# Macropad.net
KiCad netlist of a schematic drawn in EAGLE
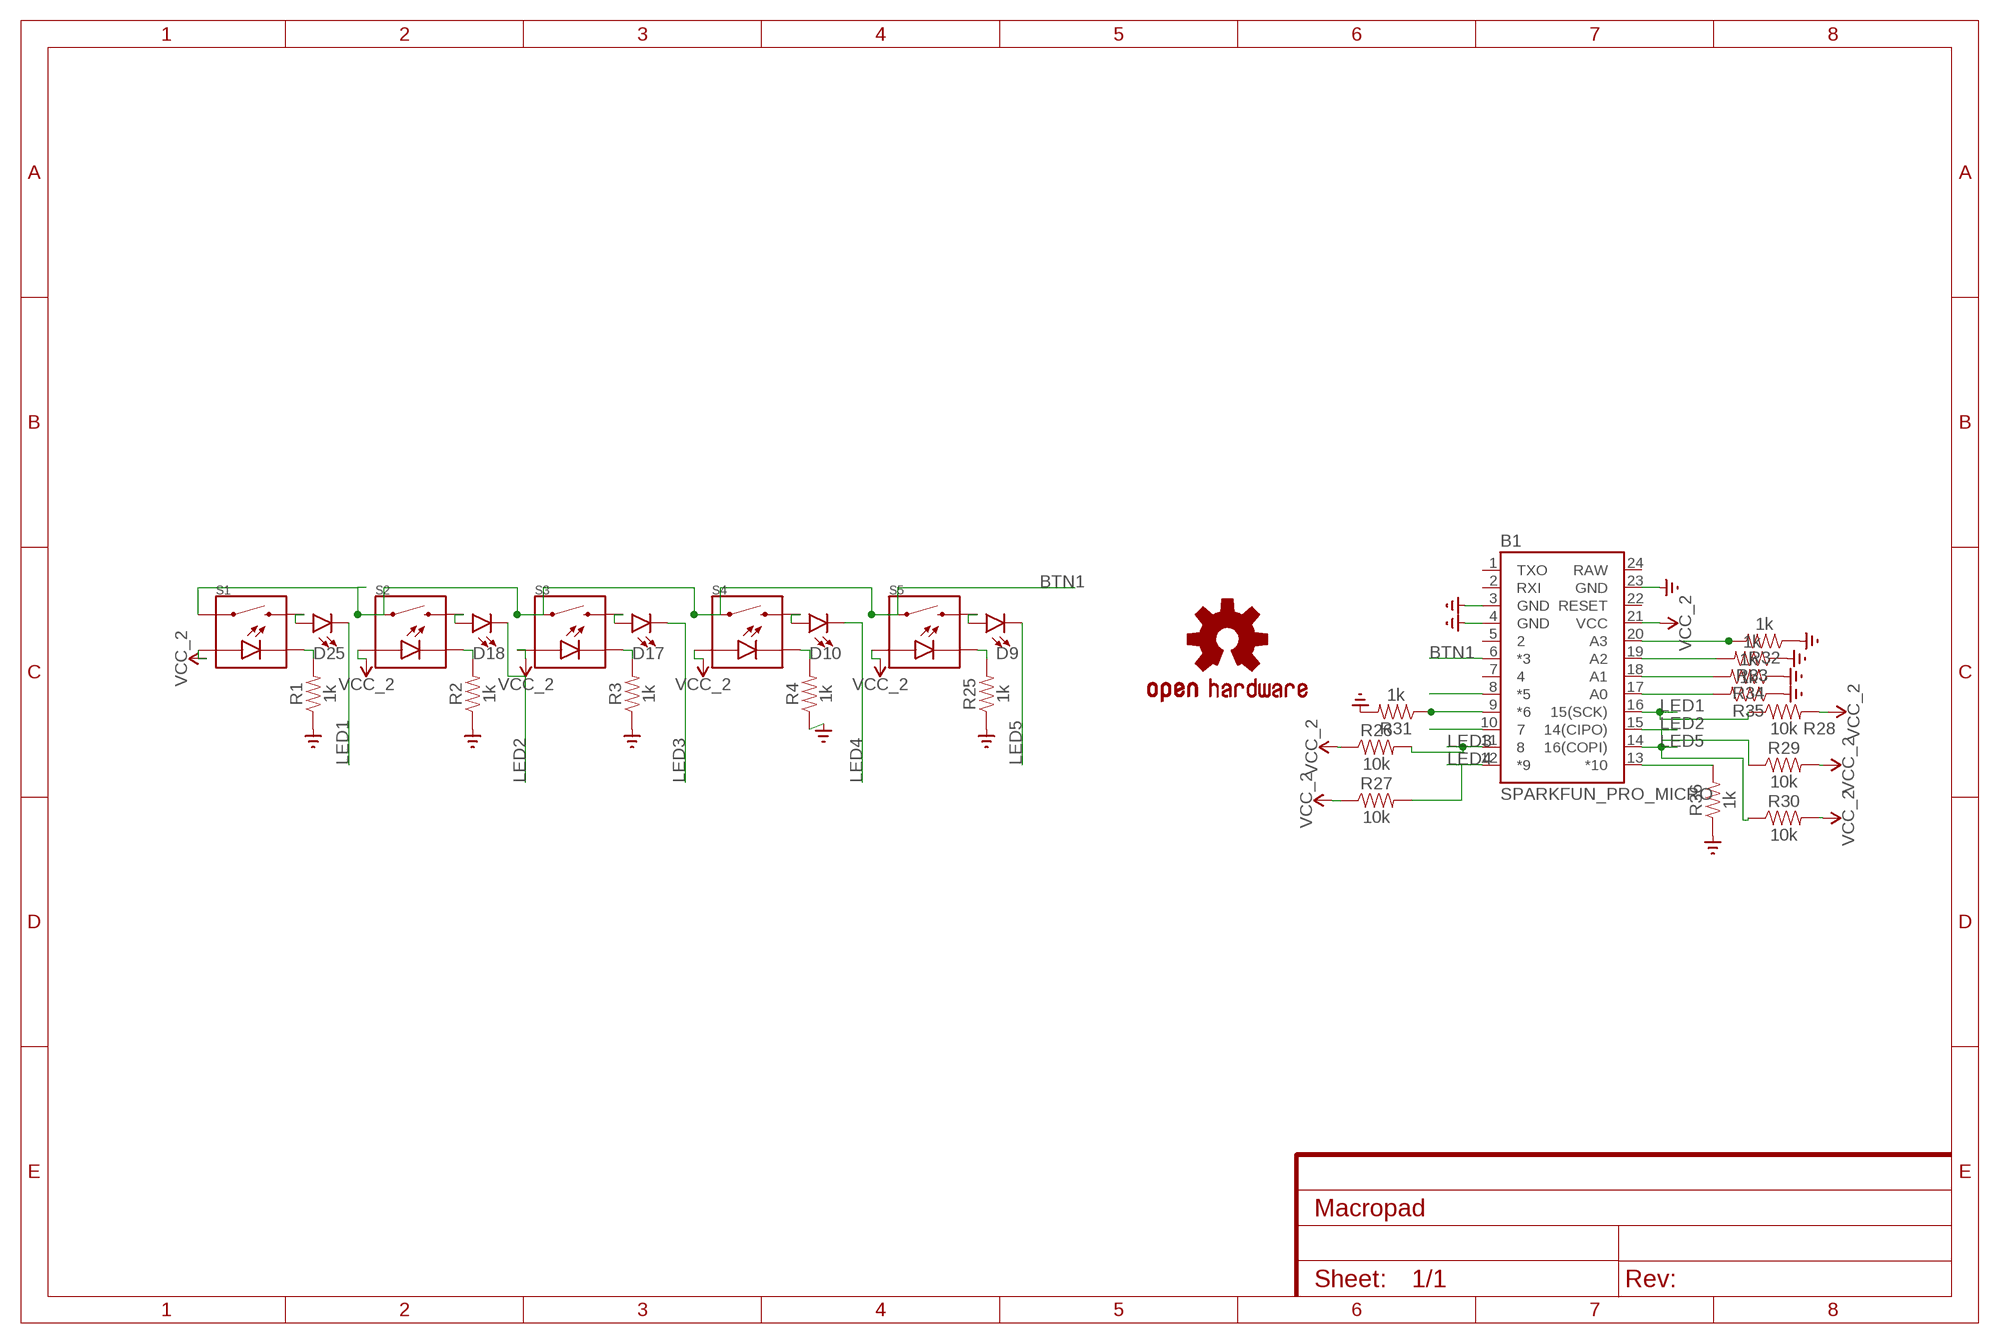
[diagram p0: schematic, sheet 1]

(export (version "E")
  (design (tool "Eeschema 10.0.6"))
  (components
    (comp (ref "B1")
      (value "SPARKFUN_PRO_MICRO")
      (footprint "eagle-import:SPARKFUN_PRO_MICRO")
      (libsource (lib "eagle-import") (part "SPARKFUN_PRO_MICRO"))
    )
    (comp (ref "D9")
      (value "LED3MM")
      (footprint "eagle-import:LED_3MM")
      (libsource (lib "eagle-import") (part "LED3MM"))
    )
    (comp (ref "D10")
      (value "LED3MM")
      (footprint "eagle-import:LED_3MM")
      (libsource (lib "eagle-import") (part "LED3MM"))
    )
    (comp (ref "D17")
      (value "LED3MM")
      (footprint "eagle-import:LED_3MM")
      (libsource (lib "eagle-import") (part "LED3MM"))
    )
    (comp (ref "D18")
      (value "LED3MM")
      (footprint "eagle-import:LED_3MM")
      (libsource (lib "eagle-import") (part "LED3MM"))
    )
    (comp (ref "D25")
      (value "LED3MM")
      (footprint "eagle-import:LED_3MM")
      (libsource (lib "eagle-import") (part "LED3MM"))
    )
    (comp (ref "LOGO1")
      (value "OSHW-LOGOM-COPPER")
      (footprint "eagle-import:OSHW-LOGO-M_COPPER")
      (libsource (lib "eagle-import") (part "OSHW-LOGOM-COPPER"))
    )
    (comp (ref "R1")
      (value "1k")
      (footprint "eagle-import:AXIAL-0.3")
      (libsource (lib "eagle-import") (part "1KOHM-HORIZ-1/4W-1%"))
    )
    (comp (ref "R2")
      (value "1k")
      (footprint "eagle-import:AXIAL-0.3")
      (libsource (lib "eagle-import") (part "1KOHM-HORIZ-1/4W-1%"))
    )
    (comp (ref "R3")
      (value "1k")
      (footprint "eagle-import:AXIAL-0.3")
      (libsource (lib "eagle-import") (part "1KOHM-HORIZ-1/4W-1%"))
    )
    (comp (ref "R4")
      (value "1k")
      (footprint "eagle-import:AXIAL-0.3")
      (libsource (lib "eagle-import") (part "1KOHM-HORIZ-1/4W-1%"))
    )
    (comp (ref "R25")
      (value "1k")
      (footprint "eagle-import:AXIAL-0.3")
      (libsource (lib "eagle-import") (part "1KOHM-HORIZ-1/4W-1%"))
    )
    (comp (ref "R26")
      (value "10k")
      (footprint "eagle-import:AXIAL-0.3")
      (libsource (lib "eagle-import") (part "10KOHM-HORIZ-1/4W-1%"))
    )
    (comp (ref "R27")
      (value "10k")
      (footprint "eagle-import:AXIAL-0.3")
      (libsource (lib "eagle-import") (part "10KOHM-HORIZ-1/4W-1%"))
    )
    (comp (ref "R28")
      (value "10k")
      (footprint "eagle-import:AXIAL-0.3")
      (libsource (lib "eagle-import") (part "10KOHM-HORIZ-1/4W-1%"))
    )
    (comp (ref "R29")
      (value "10k")
      (footprint "eagle-import:AXIAL-0.3")
      (libsource (lib "eagle-import") (part "10KOHM-HORIZ-1/4W-1%"))
    )
    (comp (ref "R30")
      (value "10k")
      (footprint "eagle-import:AXIAL-0.3")
      (libsource (lib "eagle-import") (part "10KOHM-HORIZ-1/4W-1%"))
    )
    (comp (ref "R31")
      (value "1k")
      (footprint "eagle-import:AXIAL-0.3")
      (libsource (lib "eagle-import") (part "1KOHM-HORIZ-1/4W-1%"))
    )
    (comp (ref "R32")
      (value "1k")
      (footprint "eagle-import:AXIAL-0.3")
      (libsource (lib "eagle-import") (part "1KOHM-HORIZ-1/4W-1%"))
    )
    (comp (ref "R33")
      (value "1k")
      (footprint "eagle-import:AXIAL-0.3")
      (libsource (lib "eagle-import") (part "1KOHM-HORIZ-1/4W-1%"))
    )
    (comp (ref "R34")
      (value "1k")
      (footprint "eagle-import:AXIAL-0.3")
      (libsource (lib "eagle-import") (part "1KOHM-HORIZ-1/4W-1%"))
    )
    (comp (ref "R35")
      (value "1k")
      (footprint "eagle-import:AXIAL-0.3")
      (libsource (lib "eagle-import") (part "1KOHM-HORIZ-1/4W-1%"))
    )
    (comp (ref "R36")
      (value "1k")
      (footprint "eagle-import:AXIAL-0.3")
      (libsource (lib "eagle-import") (part "1KOHM-HORIZ-1/4W-1%"))
    )
    (comp (ref "S1")
      (value "1POLE-FIXPINS-W/LED")
      (footprint "eagle-import:1POLE-FIXPINS-W_LED-EASYSOLDER")
      (libsource (lib "eagle-import") (part "1POLE-FIXPINS-W/LED"))
    )
    (comp (ref "S2")
      (value "1POLE-FIXPINS-W/LED")
      (footprint "eagle-import:1POLE-FIXPINS-W_LED-EASYSOLDER")
      (libsource (lib "eagle-import") (part "1POLE-FIXPINS-W/LED"))
    )
    (comp (ref "S3")
      (value "1POLE-FIXPINS-W/LED")
      (footprint "eagle-import:1POLE-FIXPINS-W_LED-EASYSOLDER")
      (libsource (lib "eagle-import") (part "1POLE-FIXPINS-W/LED"))
    )
    (comp (ref "S4")
      (value "1POLE-FIXPINS-W/LED")
      (footprint "eagle-import:1POLE-FIXPINS-W_LED-EASYSOLDER")
      (libsource (lib "eagle-import") (part "1POLE-FIXPINS-W/LED"))
    )
    (comp (ref "S5")
      (value "1POLE-FIXPINS-W/LED")
      (footprint "eagle-import:1POLE-FIXPINS-W_LED-EASYSOLDER")
      (libsource (lib "eagle-import") (part "1POLE-FIXPINS-W/LED"))
    )
  )
  (nets
    (net (code "1") (name "/BTN1") (class "Default")
      (node (ref "B1") (pin "6") (pinfunction "*3_6") (pintype "bidirectional"))
      (node (ref "S1") (pin "1") (pinfunction "1_1") (pintype "passive"))
      (node (ref "S2") (pin "1") (pinfunction "1_1") (pintype "passive"))
      (node (ref "S3") (pin "1") (pinfunction "1_1") (pintype "passive"))
      (node (ref "S4") (pin "1") (pinfunction "1_1") (pintype "passive"))
      (node (ref "S5") (pin "1") (pinfunction "1_1") (pintype "passive"))
    )
    (net (code "2") (name "/LED1") (class "Default")
      (node (ref "B1") (pin "16") (pinfunction "15(SCK)_16") (pintype "bidirectional"))
      (node (ref "D25") (pin "K") (pinfunction "C_K") (pintype "passive"))
      (node (ref "R28") (pin "P$1") (pinfunction "1_P$1") (pintype "passive"))
    )
    (net (code "3") (name "/LED2") (class "Default")
      (node (ref "B1") (pin "15") (pinfunction "14(CIPO)_15") (pintype "bidirectional"))
      (node (ref "D18") (pin "K") (pinfunction "C_K") (pintype "passive"))
      (node (ref "R29") (pin "P$1") (pinfunction "1_P$1") (pintype "passive"))
    )
    (net (code "4") (name "/LED3") (class "Default")
      (node (ref "B1") (pin "11") (pinfunction "8_11") (pintype "bidirectional"))
      (node (ref "D17") (pin "K") (pinfunction "C_K") (pintype "passive"))
      (node (ref "R26") (pin "P$2") (pinfunction "2_P$2") (pintype "passive"))
    )
    (net (code "5") (name "/LED4") (class "Default")
      (node (ref "B1") (pin "12") (pinfunction "*9_12") (pintype "bidirectional"))
      (node (ref "D10") (pin "K") (pinfunction "C_K") (pintype "passive"))
      (node (ref "R27") (pin "P$2") (pinfunction "2_P$2") (pintype "passive"))
    )
    (net (code "6") (name "/LED5") (class "Default")
      (node (ref "B1") (pin "14") (pinfunction "16(COPI)_14") (pintype "bidirectional"))
      (node (ref "D9") (pin "K") (pinfunction "C_K") (pintype "passive"))
      (node (ref "R30") (pin "P$1") (pinfunction "1_P$1") (pintype "passive"))
    )
    (net (code "7") (name "/RAW") (class "Default")
      (node (ref "B1") (pin "24") (pinfunction "RAW_24") (pintype "power_in"))
    )
    (net (code "8") (name "Net-(B1-*6)") (class "Default")
      (node (ref "B1") (pin "9") (pinfunction "*6_9") (pintype "bidirectional"))
      (node (ref "R31") (pin "P$1") (pinfunction "1_P$1") (pintype "passive"))
    )
    (net (code "9") (name "Net-(B1-*10)") (class "Default")
      (node (ref "B1") (pin "13") (pinfunction "*10_13") (pintype "bidirectional"))
      (node (ref "R36") (pin "P$2") (pinfunction "2_P$2") (pintype "passive"))
    )
    (net (code "10") (name "Net-(B1-A0)") (class "Default")
      (node (ref "B1") (pin "17") (pinfunction "A0_17") (pintype "bidirectional"))
      (node (ref "R35") (pin "P$2") (pinfunction "2_P$2") (pintype "passive"))
    )
    (net (code "11") (name "Net-(B1-A1)") (class "Default")
      (node (ref "B1") (pin "18") (pinfunction "A1_18") (pintype "bidirectional"))
      (node (ref "R34") (pin "P$2") (pinfunction "2_P$2") (pintype "passive"))
    )
    (net (code "12") (name "Net-(B1-A2)") (class "Default")
      (node (ref "B1") (pin "19") (pinfunction "A2_19") (pintype "bidirectional"))
      (node (ref "R33") (pin "P$2") (pinfunction "2_P$2") (pintype "passive"))
    )
    (net (code "13") (name "Net-(B1-A3)") (class "Default")
      (node (ref "B1") (pin "20") (pinfunction "A3_20") (pintype "bidirectional"))
      (node (ref "R32") (pin "P$2") (pinfunction "2_P$2") (pintype "passive"))
    )
    (net (code "14") (name "Net-(D9-PadA)") (class "Default")
      (node (ref "D9") (pin "A") (pinfunction "A_A") (pintype "passive"))
      (node (ref "S5") (pin "2") (pinfunction "2_2") (pintype "passive"))
    )
    (net (code "15") (name "Net-(D10-PadA)") (class "Default")
      (node (ref "D10") (pin "A") (pinfunction "A_A") (pintype "passive"))
      (node (ref "S4") (pin "2") (pinfunction "2_2") (pintype "passive"))
    )
    (net (code "16") (name "Net-(D17-PadA)") (class "Default")
      (node (ref "D17") (pin "A") (pinfunction "A_A") (pintype "passive"))
      (node (ref "S3") (pin "2") (pinfunction "2_2") (pintype "passive"))
    )
    (net (code "17") (name "Net-(D18-PadA)") (class "Default")
      (node (ref "D18") (pin "A") (pinfunction "A_A") (pintype "passive"))
      (node (ref "S2") (pin "2") (pinfunction "2_2") (pintype "passive"))
    )
    (net (code "18") (name "Net-(D25-PadA)") (class "Default")
      (node (ref "D25") (pin "A") (pinfunction "A_A") (pintype "passive"))
      (node (ref "S1") (pin "2") (pinfunction "2_2") (pintype "passive"))
    )
    (net (code "19") (name "Net-(R1-2)") (class "Default")
      (node (ref "R1") (pin "P$2") (pinfunction "2_P$2") (pintype "passive"))
      (node (ref "S1") (pin "4") (pinfunction "4_4") (pintype "passive"))
    )
    (net (code "20") (name "Net-(R2-2)") (class "Default")
      (node (ref "R2") (pin "P$2") (pinfunction "2_P$2") (pintype "passive"))
      (node (ref "S2") (pin "4") (pinfunction "4_4") (pintype "passive"))
    )
    (net (code "21") (name "Net-(R3-2)") (class "Default")
      (node (ref "R3") (pin "P$2") (pinfunction "2_P$2") (pintype "passive"))
      (node (ref "S3") (pin "4") (pinfunction "4_4") (pintype "passive"))
    )
    (net (code "22") (name "Net-(R4-2)") (class "Default")
      (node (ref "R4") (pin "P$2") (pinfunction "2_P$2") (pintype "passive"))
      (node (ref "S4") (pin "4") (pinfunction "4_4") (pintype "passive"))
    )
    (net (code "23") (name "Net-(R25-2)") (class "Default")
      (node (ref "R25") (pin "P$2") (pinfunction "2_P$2") (pintype "passive"))
      (node (ref "S5") (pin "4") (pinfunction "4_4") (pintype "passive"))
    )
    (net (code "24") (name "SUPPLY0_GND_") (class "Default")
      (node (ref "B1") (pin "23") (pinfunction "GND_23") (pintype "power_in"))
      (node (ref "B1") (pin "3") (pinfunction "GND_3") (pintype "power_in"))
      (node (ref "B1") (pin "4") (pinfunction "GND_4") (pintype "power_in"))
      (node (ref "R1") (pin "P$1") (pinfunction "1_P$1") (pintype "passive"))
      (node (ref "R2") (pin "P$1") (pinfunction "1_P$1") (pintype "passive"))
      (node (ref "R25") (pin "P$1") (pinfunction "1_P$1") (pintype "passive"))
      (node (ref "R3") (pin "P$1") (pinfunction "1_P$1") (pintype "passive"))
      (node (ref "R31") (pin "P$2") (pinfunction "2_P$2") (pintype "passive"))
      (node (ref "R32") (pin "P$1") (pinfunction "1_P$1") (pintype "passive"))
      (node (ref "R33") (pin "P$1") (pinfunction "1_P$1") (pintype "passive"))
      (node (ref "R34") (pin "P$1") (pinfunction "1_P$1") (pintype "passive"))
      (node (ref "R35") (pin "P$1") (pinfunction "1_P$1") (pintype "passive"))
      (node (ref "R36") (pin "P$1") (pinfunction "1_P$1") (pintype "passive"))
      (node (ref "R4") (pin "P$1") (pinfunction "1_P$1") (pintype "passive"))
    )
    (net (code "25") (name "VCC_2") (class "Default")
      (node (ref "B1") (pin "21") (pinfunction "VCC_21") (pintype "power_in"))
      (node (ref "R26") (pin "P$1") (pinfunction "1_P$1") (pintype "passive"))
      (node (ref "R27") (pin "P$1") (pinfunction "1_P$1") (pintype "passive"))
      (node (ref "R28") (pin "P$2") (pinfunction "2_P$2") (pintype "passive"))
      (node (ref "R29") (pin "P$2") (pinfunction "2_P$2") (pintype "passive"))
      (node (ref "R30") (pin "P$2") (pinfunction "2_P$2") (pintype "passive"))
      (node (ref "S1") (pin "3") (pinfunction "3_3") (pintype "passive"))
      (node (ref "S2") (pin "3") (pinfunction "3_3") (pintype "passive"))
      (node (ref "S3") (pin "3") (pinfunction "3_3") (pintype "passive"))
      (node (ref "S4") (pin "3") (pinfunction "3_3") (pintype "passive"))
      (node (ref "S5") (pin "3") (pinfunction "3_3") (pintype "passive"))
    )
    (net (code "26") (name "unconnected-(B1-*5-Pad8)") (class "Default")
      (node (ref "B1") (pin "8") (pinfunction "*5_8") (pintype "bidirectional"))
    )
    (net (code "27") (name "unconnected-(B1-2-Pad5)") (class "Default")
      (node (ref "B1") (pin "5") (pinfunction "2_5") (pintype "bidirectional"))
    )
    (net (code "28") (name "unconnected-(B1-4-Pad7)") (class "Default")
      (node (ref "B1") (pin "7") (pinfunction "4_7") (pintype "bidirectional"))
    )
    (net (code "29") (name "unconnected-(B1-7-Pad10)") (class "Default")
      (node (ref "B1") (pin "10") (pinfunction "7_10") (pintype "bidirectional"))
    )
    (net (code "30") (name "unconnected-(B1-RESET-Pad22)") (class "Default")
      (node (ref "B1") (pin "22") (pinfunction "RESET_22") (pintype "bidirectional"))
    )
    (net (code "31") (name "unconnected-(B1-RXI-Pad2)") (class "Default")
      (node (ref "B1") (pin "2") (pinfunction "RXI_2") (pintype "bidirectional"))
    )
    (net (code "32") (name "unconnected-(B1-TXO-Pad1)") (class "Default")
      (node (ref "B1") (pin "1") (pinfunction "TXO_1") (pintype "bidirectional"))
    )
  )
)
